# LIS3DH.net
KiCad netlist of a schematic drawn in Altium Designer
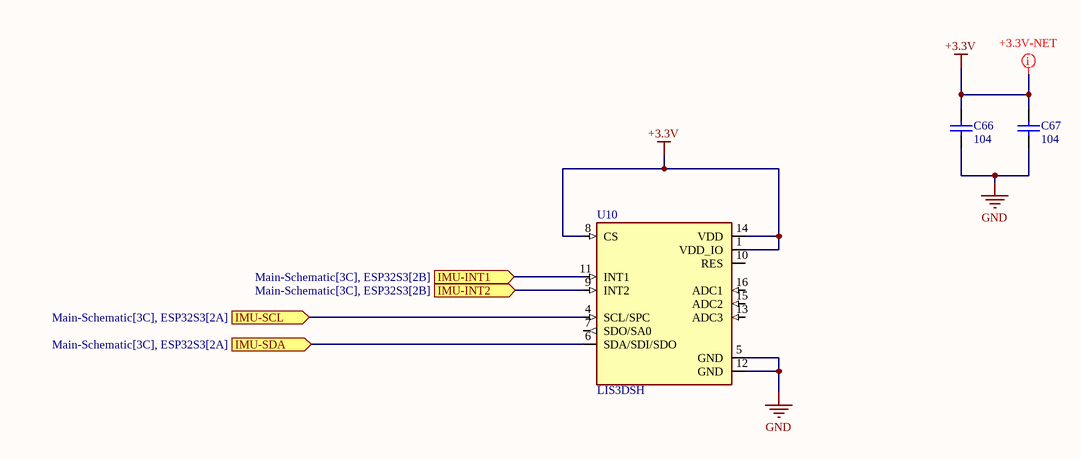
[diagram p0: LIS3DH.SchDoc]

(export (version "E")
  (design (tool "Eeschema 10.0.6"))
  (components
    (comp (ref "C66")
      (value "104")
      (footprint "CAP_0603")
      (description "Non-polarized capacitor")
      (libsource (lib "Capacitor") (part "Cap_NP"))
    )
    (comp (ref "C67")
      (value "104")
      (footprint "CAP_0603")
      (description "Non-polarized capacitor")
      (libsource (lib "Capacitor") (part "Cap_NP"))
    )
    (comp (ref "U10")
      (value "LIS3DSH")
      (footprint "LGA16R50P5X3_300X300X100N")
      (description "Accelerometer X, Y, Z Axis Â±2g, 4g, 6g, 8g, 16g 1.56Hz ~ 800Hz 16-LGA _3x3_")
      (fields (field (name "MF") "STMicroelectronics"))
      (libsource (lib "LIS3DSH") (part "LIS3DSH"))
    )
  )
  (nets
    (net (code "1") (name "+3.3V") (class "Default")
      (node (ref "C66") (pin "2") (pinfunction "2_2") (pintype "passive"))
      (node (ref "C67") (pin "2") (pinfunction "2_2") (pintype "passive"))
      (node (ref "U10") (pin "1") (pinfunction "VDD_IO_1") (pintype "power_in"))
      (node (ref "U10") (pin "14") (pinfunction "VDD_14") (pintype "power_in"))
      (node (ref "U10") (pin "8") (pinfunction "CS_8") (pintype "input"))
    )
    (net (code "2") (name "/IMU-INT1") (class "Default")
      (node (ref "U10") (pin "11") (pinfunction "INT1_11") (pintype "input"))
    )
    (net (code "3") (name "/IMU-INT2") (class "Default")
      (node (ref "U10") (pin "9") (pinfunction "INT2_9") (pintype "input"))
    )
    (net (code "4") (name "/IMU-SCL") (class "Default")
      (node (ref "U10") (pin "4") (pinfunction "SCL/SPC_4") (pintype "input"))
    )
    (net (code "5") (name "/IMU-SDA") (class "Default")
      (node (ref "U10") (pin "6") (pinfunction "SDA/SDI/SDO_6") (pintype "bidirectional"))
    )
    (net (code "6") (name "GND") (class "Default")
      (node (ref "C66") (pin "1") (pinfunction "1_1") (pintype "passive"))
      (node (ref "C67") (pin "1") (pinfunction "1_1") (pintype "passive"))
      (node (ref "U10") (pin "12") (pinfunction "GND_12") (pintype "power_in"))
      (node (ref "U10") (pin "5") (pinfunction "GND_5") (pintype "power_in"))
    )
    (net (code "7") (name "unconnected-(U10-ADC1-Pad16)") (class "Default")
      (node (ref "U10") (pin "16") (pinfunction "ADC1_16") (pintype "input"))
    )
    (net (code "8") (name "unconnected-(U10-ADC2-Pad15)") (class "Default")
      (node (ref "U10") (pin "15") (pinfunction "ADC2_15") (pintype "input"))
    )
    (net (code "9") (name "unconnected-(U10-ADC3-Pad13)") (class "Default")
      (node (ref "U10") (pin "13") (pinfunction "ADC3_13") (pintype "input"))
    )
    (net (code "10") (name "unconnected-(U10-RES-Pad10)") (class "Default")
      (node (ref "U10") (pin "10") (pinfunction "RES_10") (pintype "power_in"))
    )
    (net (code "11") (name "unconnected-(U10-SDO{slash}SA0-Pad7)") (class "Default")
      (node (ref "U10") (pin "7") (pinfunction "SDO/SA0_7") (pintype "output"))
    )
  )
)
